# quadrotor.net
KiCad netlist of a schematic drawn in EAGLE
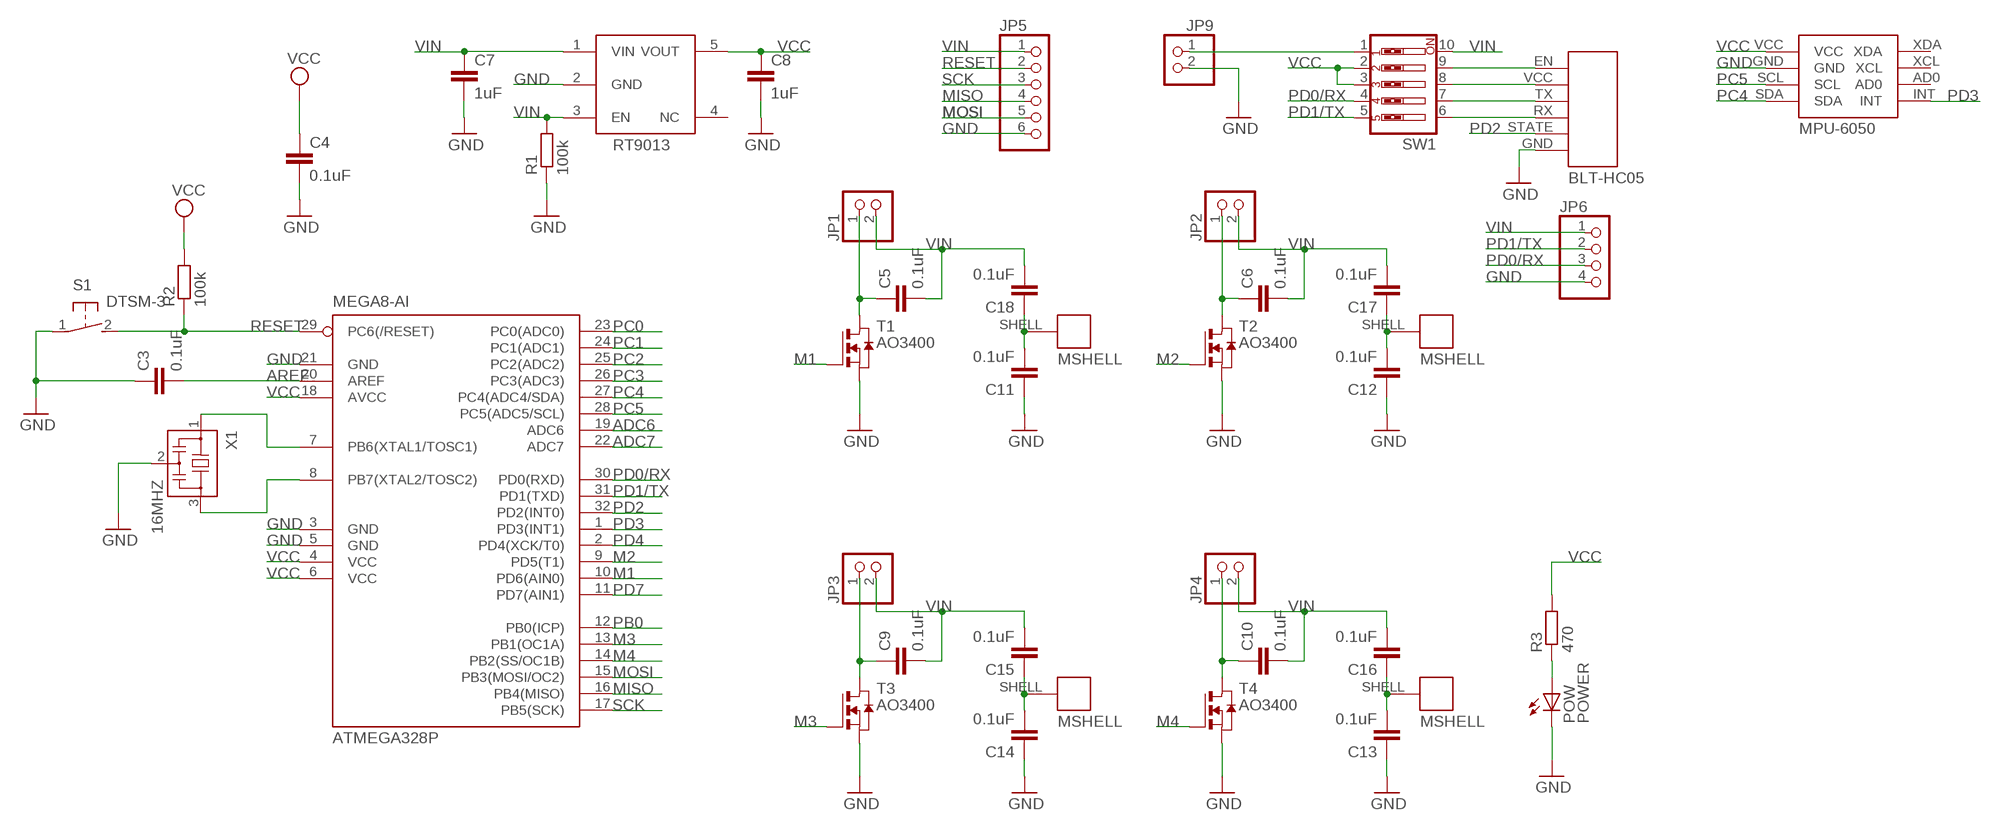
[diagram p0: schematic, sheet 1]

(export (version "E")
  (design (tool "Eeschema 10.0.6"))
  (components
    (comp (ref "ATMEGA328P")
      (value "MEGA8-AI")
      (footprint "eagle-import:TQFP32-08")
      (fields (field (name "MPN") "ATMEGA8-16AU"))
      (libsource (lib "eagle-import") (part "MEGA8-AI"))
    )
    (comp (ref "C3")
      (value "0.1uF")
      (footprint "eagle-import:C0603")
      (libsource (lib "eagle-import") (part "CC0603"))
    )
    (comp (ref "C4")
      (value "0.1uF")
      (footprint "eagle-import:C0603")
      (libsource (lib "eagle-import") (part "CC0603"))
    )
    (comp (ref "C5")
      (value "0.1uF")
      (footprint "eagle-import:C0603")
      (libsource (lib "eagle-import") (part "CC0603"))
    )
    (comp (ref "C6")
      (value "0.1uF")
      (footprint "eagle-import:C0603")
      (libsource (lib "eagle-import") (part "CC0603"))
    )
    (comp (ref "C7")
      (value "1uF")
      (footprint "eagle-import:C0603")
      (libsource (lib "eagle-import") (part "CC0603"))
    )
    (comp (ref "C8")
      (value "1uF")
      (footprint "eagle-import:C0603")
      (libsource (lib "eagle-import") (part "CC0603"))
    )
    (comp (ref "C9")
      (value "0.1uF")
      (footprint "eagle-import:C0603")
      (libsource (lib "eagle-import") (part "CC0603"))
    )
    (comp (ref "C10")
      (value "0.1uF")
      (footprint "eagle-import:C0603")
      (libsource (lib "eagle-import") (part "CC0603"))
    )
    (comp (ref "C11")
      (value "0.1uF")
      (footprint "eagle-import:C0603")
      (libsource (lib "eagle-import") (part "CC0603"))
    )
    (comp (ref "C12")
      (value "0.1uF")
      (footprint "eagle-import:C0603")
      (libsource (lib "eagle-import") (part "CC0603"))
    )
    (comp (ref "C13")
      (value "0.1uF")
      (footprint "eagle-import:C0603")
      (libsource (lib "eagle-import") (part "CC0603"))
    )
    (comp (ref "C14")
      (value "0.1uF")
      (footprint "eagle-import:C0603")
      (libsource (lib "eagle-import") (part "CC0603"))
    )
    (comp (ref "C15")
      (value "0.1uF")
      (footprint "eagle-import:C0603")
      (libsource (lib "eagle-import") (part "CC0603"))
    )
    (comp (ref "C16")
      (value "0.1uF")
      (footprint "eagle-import:C0603")
      (libsource (lib "eagle-import") (part "CC0603"))
    )
    (comp (ref "C17")
      (value "0.1uF")
      (footprint "eagle-import:C0603")
      (libsource (lib "eagle-import") (part "CC0603"))
    )
    (comp (ref "C18")
      (value "0.1uF")
      (footprint "eagle-import:C0603")
      (libsource (lib "eagle-import") (part "CC0603"))
    )
    (comp (ref "JP1")
      (value "PINHD-1X2")
      (footprint "eagle-import:1X02")
      (libsource (lib "eagle-import") (part "PINHD-1X2"))
    )
    (comp (ref "JP2")
      (value "PINHD-1X2")
      (footprint "eagle-import:1X02")
      (libsource (lib "eagle-import") (part "PINHD-1X2"))
    )
    (comp (ref "JP3")
      (value "PINHD-1X2")
      (footprint "eagle-import:1X02")
      (libsource (lib "eagle-import") (part "PINHD-1X2"))
    )
    (comp (ref "JP4")
      (value "PINHD-1X2")
      (footprint "eagle-import:1X02")
      (libsource (lib "eagle-import") (part "PINHD-1X2"))
    )
    (comp (ref "JP5")
      (value "PINHD-1X6")
      (footprint "eagle-import:1X06")
      (libsource (lib "eagle-import") (part "PINHD-1X6"))
    )
    (comp (ref "JP6")
      (value "PINHD-1X4")
      (footprint "eagle-import:1X04")
      (libsource (lib "eagle-import") (part "PINHD-1X4"))
    )
    (comp (ref "JP9")
      (value "PINHD-1X2")
      (footprint "eagle-import:1X02")
      (libsource (lib "eagle-import") (part "PINHD-1X2"))
    )
    (comp (ref "POW")
      (value "POWER")
      (footprint "eagle-import:LED_SML0603")
      (libsource (lib "eagle-import") (part "LED_ESML0603"))
    )
    (comp (ref "R1")
      (value "100k")
      (footprint "eagle-import:R0603")
      (libsource (lib "eagle-import") (part "RR0603"))
    )
    (comp (ref "R2")
      (value "100k")
      (footprint "eagle-import:R0603")
      (libsource (lib "eagle-import") (part "RR0603"))
    )
    (comp (ref "R3")
      (value "470")
      (footprint "eagle-import:R0603")
      (libsource (lib "eagle-import") (part "RR0603"))
    )
    (comp (ref "S1")
      (value "DTSM-3")
      (footprint "eagle-import:DTSM-3")
      (libsource (lib "eagle-import") (part "DTSM-3"))
    )
    (comp (ref "SW1")
      (value "SW_DIP-5")
      (footprint "eagle-import:EDG-05")
      (libsource (lib "eagle-import") (part "SW_DIP-5"))
    )
    (comp (ref "T1")
      (value "AO3400")
      (footprint "eagle-import:SOT-23")
      (libsource (lib "eagle-import") (part "NMOSSOT23"))
    )
    (comp (ref "T2")
      (value "AO3400")
      (footprint "eagle-import:SOT-23")
      (libsource (lib "eagle-import") (part "NMOSSOT23"))
    )
    (comp (ref "T3")
      (value "AO3400")
      (footprint "eagle-import:SOT-23")
      (libsource (lib "eagle-import") (part "NMOSSOT23"))
    )
    (comp (ref "T4")
      (value "AO3400")
      (footprint "eagle-import:SOT-23")
      (libsource (lib "eagle-import") (part "NMOSSOT23"))
    )
    (comp (ref "U$1")
      (value "RT9013")
      (footprint "eagle-import:SOT-23-5")
      (libsource (lib "eagle-import") (part "RT9013"))
    )
    (comp (ref "U$2")
      (value "BLT-HC05")
      (footprint "eagle-import:BLT-HC05")
      (libsource (lib "eagle-import") (part "BLT-HC05"))
    )
    (comp (ref "U$3")
      (value "720-MSHELL")
      (footprint "eagle-import:720MOTOR")
      (libsource (lib "eagle-import") (part "720-MSHELL"))
    )
    (comp (ref "U$4")
      (value "720-MSHELL")
      (footprint "eagle-import:720MOTOR")
      (libsource (lib "eagle-import") (part "720-MSHELL"))
    )
    (comp (ref "U$5")
      (value "720-MSHELL")
      (footprint "eagle-import:720MOTOR")
      (libsource (lib "eagle-import") (part "720-MSHELL"))
    )
    (comp (ref "U$6")
      (value "720-MSHELL")
      (footprint "eagle-import:720MOTOR")
      (libsource (lib "eagle-import") (part "720-MSHELL"))
    )
    (comp (ref "U$7")
      (value "MPU-6050")
      (footprint "eagle-import:MPU-6050")
      (libsource (lib "eagle-import") (part "MPU-6050"))
    )
    (comp (ref "X1")
      (value "16MHZ")
      (footprint "eagle-import:CSTCR6M")
      (fields (field (name "MPN") "CSTCR6M00G53-R0"))
      (libsource (lib "eagle-import") (part "CSTCR6M00G53Z"))
    )
  )
  (nets
    (net (code "1") (name "/ADC6") (class "Default")
      (node (ref "ATMEGA328P") (pin "19") (pinfunction "ADC6_19") (pintype "bidirectional"))
    )
    (net (code "2") (name "/ADC7") (class "Default")
      (node (ref "ATMEGA328P") (pin "22") (pinfunction "ADC7_22") (pintype "bidirectional"))
    )
    (net (code "3") (name "/AREF") (class "Default")
      (node (ref "ATMEGA328P") (pin "20") (pinfunction "AREF_20") (pintype "passive"))
      (node (ref "C3") (pin "2") (pinfunction "2_2") (pintype "passive"))
    )
    (net (code "4") (name "/M1") (class "Default")
      (node (ref "ATMEGA328P") (pin "10") (pinfunction "PD6(AIN0)_10") (pintype "bidirectional"))
      (node (ref "T1") (pin "3") (pinfunction "G_3") (pintype "passive"))
    )
    (net (code "5") (name "/M2") (class "Default")
      (node (ref "ATMEGA328P") (pin "9") (pinfunction "PD5(T1)_9") (pintype "bidirectional"))
      (node (ref "T2") (pin "3") (pinfunction "G_3") (pintype "passive"))
    )
    (net (code "6") (name "/M3") (class "Default")
      (node (ref "ATMEGA328P") (pin "13") (pinfunction "PB1(OC1A)_13") (pintype "bidirectional"))
      (node (ref "T3") (pin "3") (pinfunction "G_3") (pintype "passive"))
    )
    (net (code "7") (name "/M4") (class "Default")
      (node (ref "ATMEGA328P") (pin "14") (pinfunction "PB2(SS/OC1B)_14") (pintype "bidirectional"))
      (node (ref "T4") (pin "3") (pinfunction "G_3") (pintype "passive"))
    )
    (net (code "8") (name "/MISO") (class "Default")
      (node (ref "ATMEGA328P") (pin "16") (pinfunction "PB4(MISO)_16") (pintype "bidirectional"))
      (node (ref "JP5") (pin "4") (pinfunction "4_4") (pintype "passive"))
    )
    (net (code "9") (name "/MOSI") (class "Default")
      (node (ref "ATMEGA328P") (pin "15") (pinfunction "PB3(MOSI/OC2)_15") (pintype "bidirectional"))
      (node (ref "JP5") (pin "5") (pinfunction "5_5") (pintype "passive"))
    )
    (net (code "10") (name "/PB0") (class "Default")
      (node (ref "ATMEGA328P") (pin "12") (pinfunction "PB0(ICP)_12") (pintype "bidirectional"))
    )
    (net (code "11") (name "/PC0") (class "Default")
      (node (ref "ATMEGA328P") (pin "23") (pinfunction "PC0(ADC0)_23") (pintype "bidirectional"))
    )
    (net (code "12") (name "/PC1") (class "Default")
      (node (ref "ATMEGA328P") (pin "24") (pinfunction "PC1(ADC1)_24") (pintype "bidirectional"))
    )
    (net (code "13") (name "/PC2") (class "Default")
      (node (ref "ATMEGA328P") (pin "25") (pinfunction "PC2(ADC2)_25") (pintype "bidirectional"))
    )
    (net (code "14") (name "/PC3") (class "Default")
      (node (ref "ATMEGA328P") (pin "26") (pinfunction "PC3(ADC3)_26") (pintype "bidirectional"))
    )
    (net (code "15") (name "/PC4") (class "Default")
      (node (ref "ATMEGA328P") (pin "27") (pinfunction "PC4(ADC4/SDA)_27") (pintype "bidirectional"))
      (node (ref "U$7") (pin "SDA") (pinfunction "SDA_SDA") (pintype "bidirectional"))
    )
    (net (code "16") (name "/PC5") (class "Default")
      (node (ref "ATMEGA328P") (pin "28") (pinfunction "PC5(ADC5/SCL)_28") (pintype "bidirectional"))
      (node (ref "U$7") (pin "SCL") (pinfunction "SCL_SCL") (pintype "bidirectional"))
    )
    (net (code "17") (name "/PD0{slash}RX") (class "Default")
      (node (ref "ATMEGA328P") (pin "30") (pinfunction "PD0(RXD)_30") (pintype "bidirectional"))
      (node (ref "JP6") (pin "3") (pinfunction "3_3") (pintype "passive"))
      (node (ref "SW1") (pin "4") (pinfunction "4_4") (pintype "passive"))
    )
    (net (code "18") (name "/PD1{slash}TX") (class "Default")
      (node (ref "ATMEGA328P") (pin "31") (pinfunction "PD1(TXD)_31") (pintype "bidirectional"))
      (node (ref "JP6") (pin "2") (pinfunction "2_2") (pintype "passive"))
      (node (ref "SW1") (pin "5") (pinfunction "5_5") (pintype "passive"))
    )
    (net (code "19") (name "/PD2") (class "Default")
      (node (ref "ATMEGA328P") (pin "32") (pinfunction "PD2(INT0)_32") (pintype "bidirectional"))
      (node (ref "U$2") (pin "STATE") (pinfunction "STATE_STATE") (pintype "bidirectional"))
    )
    (net (code "20") (name "/PD3") (class "Default")
      (node (ref "ATMEGA328P") (pin "1") (pinfunction "PD3(INT1)_1") (pintype "bidirectional"))
      (node (ref "U$7") (pin "INT") (pinfunction "INT_INT") (pintype "bidirectional"))
    )
    (net (code "21") (name "/PD4") (class "Default")
      (node (ref "ATMEGA328P") (pin "2") (pinfunction "PD4(XCK/T0)_2") (pintype "bidirectional"))
    )
    (net (code "22") (name "/PD7") (class "Default")
      (node (ref "ATMEGA328P") (pin "11") (pinfunction "PD7(AIN1)_11") (pintype "bidirectional"))
    )
    (net (code "23") (name "/RESET") (class "Default")
      (node (ref "ATMEGA328P") (pin "29") (pinfunction "PC6(/RESET)_29") (pintype "bidirectional"))
      (node (ref "JP5") (pin "2") (pinfunction "2_2") (pintype "passive"))
      (node (ref "R2") (pin "1") (pinfunction "1_1") (pintype "passive"))
      (node (ref "S1") (pin "2") (pinfunction "2_2") (pintype "passive"))
    )
    (net (code "24") (name "/SCK") (class "Default")
      (node (ref "ATMEGA328P") (pin "17") (pinfunction "PB5(SCK)_17") (pintype "bidirectional"))
      (node (ref "JP5") (pin "3") (pinfunction "3_3") (pintype "passive"))
    )
    (net (code "25") (name "/VIN") (class "Default")
      (node (ref "C10") (pin "2") (pinfunction "2_2") (pintype "passive"))
      (node (ref "C15") (pin "2") (pinfunction "2_2") (pintype "passive"))
      (node (ref "C16") (pin "2") (pinfunction "2_2") (pintype "passive"))
      (node (ref "C17") (pin "2") (pinfunction "2_2") (pintype "passive"))
      (node (ref "C18") (pin "2") (pinfunction "2_2") (pintype "passive"))
      (node (ref "C5") (pin "2") (pinfunction "2_2") (pintype "passive"))
      (node (ref "C6") (pin "2") (pinfunction "2_2") (pintype "passive"))
      (node (ref "C7") (pin "1") (pinfunction "1_1") (pintype "passive"))
      (node (ref "C9") (pin "2") (pinfunction "2_2") (pintype "passive"))
      (node (ref "JP1") (pin "2") (pinfunction "2_2") (pintype "passive"))
      (node (ref "JP2") (pin "2") (pinfunction "2_2") (pintype "passive"))
      (node (ref "JP3") (pin "2") (pinfunction "2_2") (pintype "passive"))
      (node (ref "JP4") (pin "2") (pinfunction "2_2") (pintype "passive"))
      (node (ref "JP5") (pin "1") (pinfunction "1_1") (pintype "passive"))
      (node (ref "JP6") (pin "1") (pinfunction "1_1") (pintype "passive"))
      (node (ref "R1") (pin "2") (pinfunction "2_2") (pintype "passive"))
      (node (ref "SW1") (pin "10") (pinfunction "10_10") (pintype "passive"))
      (node (ref "U$1") (pin "1") (pinfunction "VIN_1") (pintype "bidirectional"))
      (node (ref "U$1") (pin "3") (pinfunction "EN_3") (pintype "bidirectional"))
    )
    (net (code "26") (name "GND") (class "Default")
      (node (ref "ATMEGA328P") (pin "21") (pinfunction "GND_21") (pintype "power_in"))
      (node (ref "ATMEGA328P") (pin "3") (pinfunction "GND_3") (pintype "power_in"))
      (node (ref "ATMEGA328P") (pin "5") (pinfunction "GND_5") (pintype "power_in"))
      (node (ref "C11") (pin "1") (pinfunction "1_1") (pintype "passive"))
      (node (ref "C12") (pin "1") (pinfunction "1_1") (pintype "passive"))
      (node (ref "C13") (pin "1") (pinfunction "1_1") (pintype "passive"))
      (node (ref "C14") (pin "1") (pinfunction "1_1") (pintype "passive"))
      (node (ref "C3") (pin "1") (pinfunction "1_1") (pintype "passive"))
      (node (ref "C4") (pin "2") (pinfunction "2_2") (pintype "passive"))
      (node (ref "C7") (pin "2") (pinfunction "2_2") (pintype "passive"))
      (node (ref "C8") (pin "2") (pinfunction "2_2") (pintype "passive"))
      (node (ref "JP5") (pin "6") (pinfunction "6_6") (pintype "passive"))
      (node (ref "JP6") (pin "4") (pinfunction "4_4") (pintype "passive"))
      (node (ref "JP9") (pin "2") (pinfunction "2_2") (pintype "passive"))
      (node (ref "POW") (pin "C") (pinfunction "C_C") (pintype "passive"))
      (node (ref "R1") (pin "1") (pinfunction "1_1") (pintype "passive"))
      (node (ref "S1") (pin "1") (pinfunction "1_1") (pintype "passive"))
      (node (ref "T1") (pin "2") (pinfunction "S_2") (pintype "passive"))
      (node (ref "T2") (pin "2") (pinfunction "S_2") (pintype "passive"))
      (node (ref "T3") (pin "2") (pinfunction "S_2") (pintype "passive"))
      (node (ref "T4") (pin "2") (pinfunction "S_2") (pintype "passive"))
      (node (ref "U$1") (pin "2") (pinfunction "GND_2") (pintype "bidirectional"))
      (node (ref "U$2") (pin "GND") (pinfunction "GND_GND") (pintype "bidirectional"))
      (node (ref "U$7") (pin "GND") (pinfunction "GND_GND") (pintype "bidirectional"))
      (node (ref "X1") (pin "2") (pinfunction "2_2") (pintype "passive"))
    )
    (net (code "27") (name "Net-(ATMEGA328P-PB6(XTAL1{slash}TOSC1))") (class "Default")
      (node (ref "ATMEGA328P") (pin "7") (pinfunction "PB6(XTAL1/TOSC1)_7") (pintype "bidirectional"))
      (node (ref "X1") (pin "1") (pinfunction "1_1") (pintype "passive"))
    )
    (net (code "28") (name "Net-(ATMEGA328P-PB7(XTAL2{slash}TOSC2))") (class "Default")
      (node (ref "ATMEGA328P") (pin "8") (pinfunction "PB7(XTAL2/TOSC2)_8") (pintype "bidirectional"))
      (node (ref "X1") (pin "3") (pinfunction "3_3") (pintype "passive"))
    )
    (net (code "29") (name "Net-(C11-Pad2)") (class "Default")
      (node (ref "C11") (pin "2") (pinfunction "2_2") (pintype "passive"))
      (node (ref "C18") (pin "1") (pinfunction "1_1") (pintype "passive"))
      (node (ref "U$3") (pin "SHELL") (pinfunction "SHELL_SHELL") (pintype "bidirectional"))
    )
    (net (code "30") (name "Net-(C12-Pad2)") (class "Default")
      (node (ref "C12") (pin "2") (pinfunction "2_2") (pintype "passive"))
      (node (ref "C17") (pin "1") (pinfunction "1_1") (pintype "passive"))
      (node (ref "U$4") (pin "SHELL") (pinfunction "SHELL_SHELL") (pintype "bidirectional"))
    )
    (net (code "31") (name "Net-(C13-Pad2)") (class "Default")
      (node (ref "C13") (pin "2") (pinfunction "2_2") (pintype "passive"))
      (node (ref "C16") (pin "1") (pinfunction "1_1") (pintype "passive"))
      (node (ref "U$6") (pin "SHELL") (pinfunction "SHELL_SHELL") (pintype "bidirectional"))
    )
    (net (code "32") (name "Net-(C14-Pad2)") (class "Default")
      (node (ref "C14") (pin "2") (pinfunction "2_2") (pintype "passive"))
      (node (ref "C15") (pin "1") (pinfunction "1_1") (pintype "passive"))
      (node (ref "U$5") (pin "SHELL") (pinfunction "SHELL_SHELL") (pintype "bidirectional"))
    )
    (net (code "33") (name "Net-(JP9-Pad1)") (class "Default")
      (node (ref "JP9") (pin "1") (pinfunction "1_1") (pintype "passive"))
      (node (ref "SW1") (pin "1") (pinfunction "1_1") (pintype "passive"))
    )
    (net (code "34") (name "Net-(POW-PadA)") (class "Default")
      (node (ref "POW") (pin "A") (pinfunction "A_A") (pintype "passive"))
      (node (ref "R3") (pin "1") (pinfunction "1_1") (pintype "passive"))
    )
    (net (code "35") (name "Net-(SW1-Pad6)") (class "Default")
      (node (ref "SW1") (pin "6") (pinfunction "6_6") (pintype "passive"))
      (node (ref "U$2") (pin "RX") (pinfunction "RX_RX") (pintype "bidirectional"))
    )
    (net (code "36") (name "Net-(SW1-Pad7)") (class "Default")
      (node (ref "SW1") (pin "7") (pinfunction "7_7") (pintype "passive"))
      (node (ref "U$2") (pin "TX") (pinfunction "TX_TX") (pintype "bidirectional"))
    )
    (net (code "37") (name "Net-(SW1-Pad8)") (class "Default")
      (node (ref "SW1") (pin "8") (pinfunction "8_8") (pintype "passive"))
      (node (ref "U$2") (pin "VCC") (pinfunction "VCC_VCC") (pintype "bidirectional"))
    )
    (net (code "38") (name "Net-(SW1-Pad9)") (class "Default")
      (node (ref "SW1") (pin "9") (pinfunction "9_9") (pintype "passive"))
      (node (ref "U$2") (pin "EN") (pinfunction "EN_EN") (pintype "bidirectional"))
    )
    (net (code "39") (name "Net-(T1-D)") (class "Default")
      (node (ref "C5") (pin "1") (pinfunction "1_1") (pintype "passive"))
      (node (ref "JP1") (pin "1") (pinfunction "1_1") (pintype "passive"))
      (node (ref "T1") (pin "1") (pinfunction "D_1") (pintype "passive"))
    )
    (net (code "40") (name "Net-(T2-D)") (class "Default")
      (node (ref "C6") (pin "1") (pinfunction "1_1") (pintype "passive"))
      (node (ref "JP2") (pin "1") (pinfunction "1_1") (pintype "passive"))
      (node (ref "T2") (pin "1") (pinfunction "D_1") (pintype "passive"))
    )
    (net (code "41") (name "Net-(T3-D)") (class "Default")
      (node (ref "C9") (pin "1") (pinfunction "1_1") (pintype "passive"))
      (node (ref "JP3") (pin "1") (pinfunction "1_1") (pintype "passive"))
      (node (ref "T3") (pin "1") (pinfunction "D_1") (pintype "passive"))
    )
    (net (code "42") (name "Net-(T4-D)") (class "Default")
      (node (ref "C10") (pin "1") (pinfunction "1_1") (pintype "passive"))
      (node (ref "JP4") (pin "1") (pinfunction "1_1") (pintype "passive"))
      (node (ref "T4") (pin "1") (pinfunction "D_1") (pintype "passive"))
    )
    (net (code "43") (name "VCC") (class "Default")
      (node (ref "ATMEGA328P") (pin "18") (pinfunction "AVCC_18") (pintype "power_in"))
      (node (ref "ATMEGA328P") (pin "4") (pinfunction "VCC_4") (pintype "power_in"))
      (node (ref "ATMEGA328P") (pin "6") (pinfunction "VCC_6") (pintype "power_in"))
      (node (ref "C4") (pin "1") (pinfunction "1_1") (pintype "passive"))
      (node (ref "C8") (pin "1") (pinfunction "1_1") (pintype "passive"))
      (node (ref "R2") (pin "2") (pinfunction "2_2") (pintype "passive"))
      (node (ref "R3") (pin "2") (pinfunction "2_2") (pintype "passive"))
      (node (ref "SW1") (pin "2") (pinfunction "2_2") (pintype "passive"))
      (node (ref "SW1") (pin "3") (pinfunction "3_3") (pintype "passive"))
      (node (ref "U$1") (pin "5") (pinfunction "VOUT_5") (pintype "bidirectional"))
      (node (ref "U$7") (pin "VCC") (pinfunction "VCC_VCC") (pintype "bidirectional"))
    )
    (net (code "44") (name "unconnected-(U$1-NC-Pad4)") (class "Default")
      (node (ref "U$1") (pin "4") (pinfunction "NC_4") (pintype "bidirectional"))
    )
    (net (code "45") (name "unconnected-(U$7-PadAD0)") (class "Default")
      (node (ref "U$7") (pin "AD0") (pinfunction "AD0_AD0") (pintype "bidirectional"))
    )
    (net (code "46") (name "unconnected-(U$7-PadXCL)") (class "Default")
      (node (ref "U$7") (pin "XCL") (pinfunction "XCL_XCL") (pintype "bidirectional"))
    )
    (net (code "47") (name "unconnected-(U$7-PadXDA)") (class "Default")
      (node (ref "U$7") (pin "XDA") (pinfunction "XDA_XDA") (pintype "bidirectional"))
    )
  )
)
